# SCH_SegaToys_-_ClearNote2_-_PennyCart_-_.net
KiCad netlist of a schematic drawn in EasyEDA
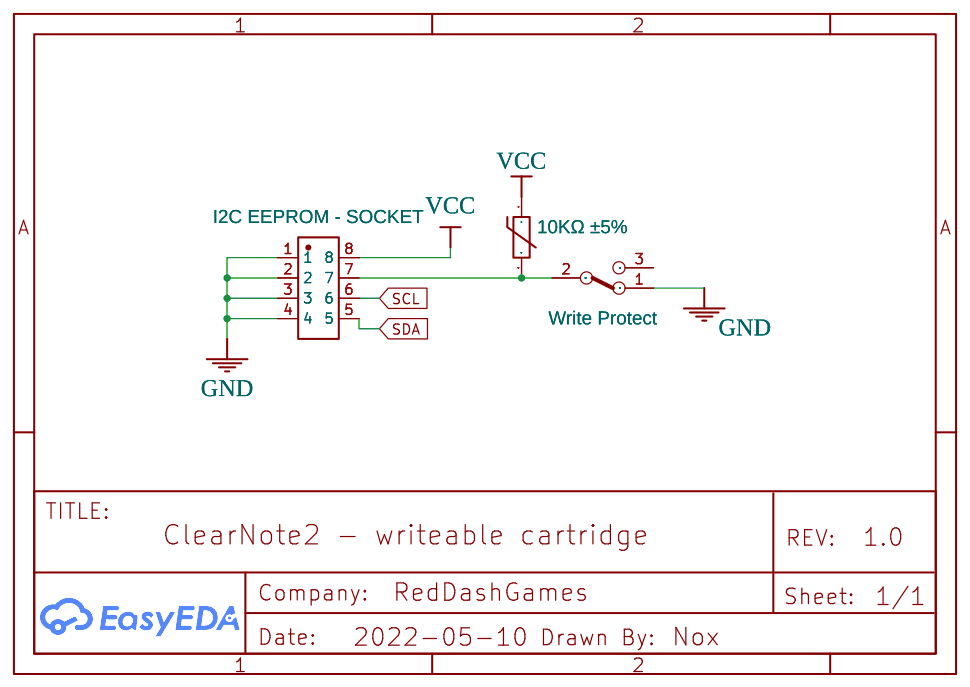
[diagram p0: schematic sheet]

(export (version "E")
  (design (tool "Eeschema 10.0.6"))
  (components
    (comp (ref "10K")
      (value "10KΩ ±5%")
      (fields
        (field (name "BOM_Manufacturer Part") "MF58 103J3470")
        (field (name "BOM_Supplier Part") "C123392")
      )
      (libsource (lib "") (part "10KΩ ±5%_MF58"))
    )
    (comp (ref "I2C-ROM")
      (value "I2C EEPROM - SOCKET")
      (fields
        (field (name "BOM_Manufacturer Part") "X5621WV-2x04-C762D1000-1000")
        (field (name "BOM_Supplier Part") "C2883629")
      )
      (libsource (lib "") (part "X5621WV-2X04-C762D1000-1000"))
    )
    (comp (ref "PROTECT")
      (value "Write Protect")
      (fields (field (name "BOM_Manufacturer Part") "Switch SPDT"))
      (libsource (lib "") (part "Slide Switch SS12D00G3"))
    )
  )
  (nets
    (net (code "1") (name "GND") (class "Default")
      (node (ref "I2C-ROM") (pin "1") (pinfunction "1_1") (pintype "unspecified"))
      (node (ref "I2C-ROM") (pin "2") (pinfunction "2_2") (pintype "unspecified"))
      (node (ref "I2C-ROM") (pin "3") (pinfunction "3_3") (pintype "unspecified"))
      (node (ref "I2C-ROM") (pin "4") (pinfunction "4_4") (pintype "unspecified"))
      (node (ref "PROTECT") (pin "1") (pinfunction "C_1") (pintype "unspecified"))
    )
    (net (code "2") (name "Net-(PROTECT-NC)") (class "Default")
      (node (ref "10K") (pin "2") (pinfunction "2_2") (pintype "unspecified"))
      (node (ref "I2C-ROM") (pin "7") (pinfunction "7_7") (pintype "unspecified"))
      (node (ref "PROTECT") (pin "2") (pinfunction "NC_2") (pintype "unspecified"))
    )
    (net (code "3") (name "SCL") (class "Default")
      (node (ref "I2C-ROM") (pin "6") (pinfunction "6_6") (pintype "unspecified"))
    )
    (net (code "4") (name "SDA") (class "Default")
      (node (ref "I2C-ROM") (pin "5") (pinfunction "5_5") (pintype "unspecified"))
    )
    (net (code "5") (name "VCC") (class "Default")
      (node (ref "10K") (pin "1") (pinfunction "1_1") (pintype "unspecified"))
      (node (ref "I2C-ROM") (pin "8") (pinfunction "8_8") (pintype "unspecified"))
    )
    (net (code "6") (name "unconnected-(PROTECT-NO-Pad3)") (class "Default")
      (node (ref "PROTECT") (pin "3") (pinfunction "NO_3") (pintype "unspecified"))
    )
  )
)
